# Schematic.net
KiCad netlist of a schematic drawn in EAGLE
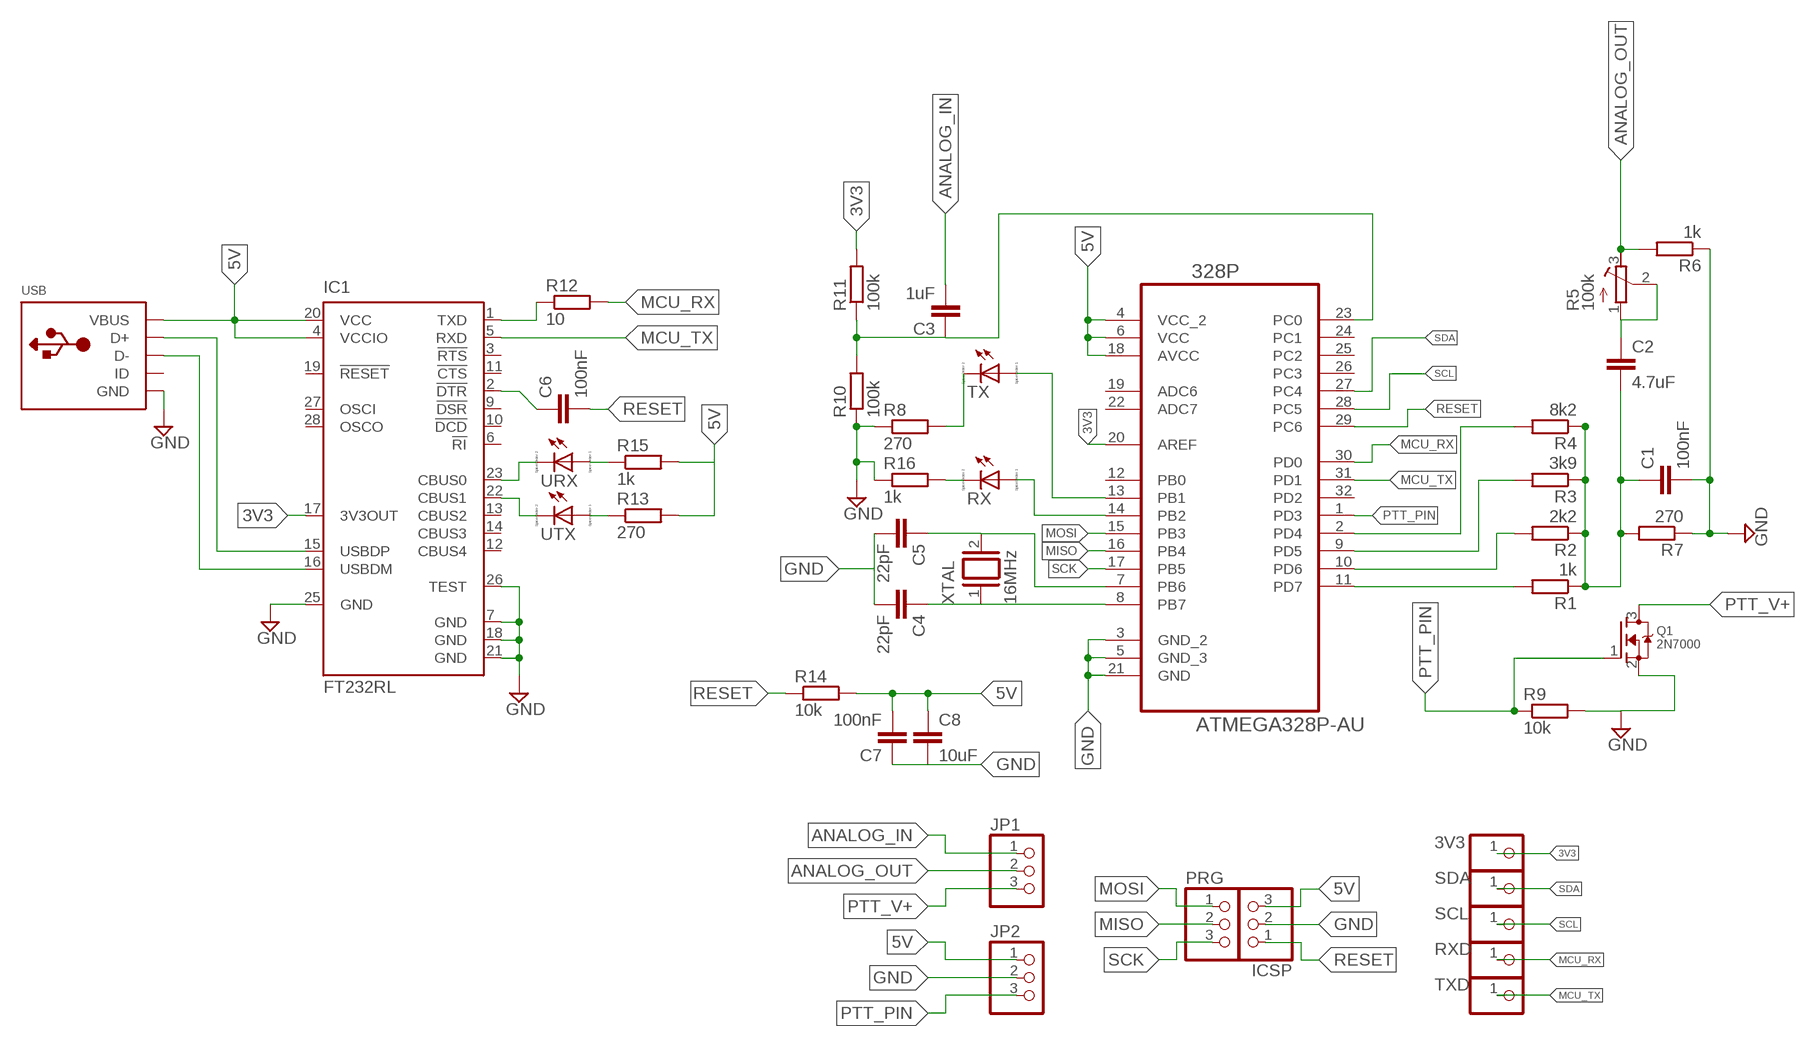
[diagram p0: schematic, sheet 1]

(export (version "E")
  (design (tool "Eeschema 10.0.6"))
  (components
    (comp (ref "3V3")
      (value "PINHD-1X1")
      (footprint "eagle-import:1X01")
      (libsource (lib "eagle-import") (part "PINHD-1X1"))
    )
    (comp (ref "328P")
      (value "ATMEGA328P-AU")
      (footprint "eagle-import:QFP80P900X900X120-32N")
      (libsource (lib "eagle-import") (part "ATMEGA328P-AU"))
    )
    (comp (ref "C1")
      (value "100nF")
      (footprint "eagle-import:C0603")
      (libsource (lib "eagle-import") (part "C-EUC0603"))
    )
    (comp (ref "C2")
      (value "4.7uF")
      (footprint "eagle-import:C0805")
      (libsource (lib "eagle-import") (part "C-EUC0805"))
    )
    (comp (ref "C3")
      (value "1uF")
      (footprint "eagle-import:C0603")
      (libsource (lib "eagle-import") (part "C-EUC0603"))
    )
    (comp (ref "C4")
      (value "22pF")
      (footprint "eagle-import:C0603")
      (libsource (lib "eagle-import") (part "C-EUC0603"))
    )
    (comp (ref "C5")
      (value "22pF")
      (footprint "eagle-import:C0603")
      (libsource (lib "eagle-import") (part "C-EUC0603"))
    )
    (comp (ref "C6")
      (value "100nF")
      (footprint "eagle-import:C0603")
      (libsource (lib "eagle-import") (part "C-EUC0603"))
    )
    (comp (ref "C7")
      (value "100nF")
      (footprint "eagle-import:C0603")
      (libsource (lib "eagle-import") (part "C-EUC0603"))
    )
    (comp (ref "C8")
      (value "10uF")
      (footprint "eagle-import:C0805")
      (libsource (lib "eagle-import") (part "C-EUC0805"))
    )
    (comp (ref "IC1")
      (value "FT232RL")
      (footprint "eagle-import:SSOP28")
      (libsource (lib "eagle-import") (part "FT232RL"))
    )
    (comp (ref "ICSP")
      (value "PINHD-1X3")
      (footprint "eagle-import:1X03")
      (libsource (lib "eagle-import") (part "PINHD-1X3"))
    )
    (comp (ref "JP1")
      (value "PINHD-1X3")
      (footprint "eagle-import:1X03")
      (libsource (lib "eagle-import") (part "PINHD-1X3"))
    )
    (comp (ref "JP2")
      (value "PINHD-1X3")
      (footprint "eagle-import:1X03")
      (libsource (lib "eagle-import") (part "PINHD-1X3"))
    )
    (comp (ref "PRG")
      (value "PINHD-1X3")
      (footprint "eagle-import:1X03")
      (libsource (lib "eagle-import") (part "PINHD-1X3"))
    )
    (comp (ref "Q1")
      (value "2N7000")
      (footprint "eagle-import:SOT23")
      (libsource (lib "eagle-import") (part "MOSFET-NREFLOW"))
    )
    (comp (ref "R1")
      (value "1k")
      (footprint "eagle-import:R0603")
      (libsource (lib "eagle-import") (part "R-EU_R0603"))
    )
    (comp (ref "R2")
      (value "2k2")
      (footprint "eagle-import:R0603")
      (libsource (lib "eagle-import") (part "R-EU_R0603"))
    )
    (comp (ref "R3")
      (value "3k9")
      (footprint "eagle-import:R0603")
      (libsource (lib "eagle-import") (part "R-EU_R0603"))
    )
    (comp (ref "R4")
      (value "8k2")
      (footprint "eagle-import:R0603")
      (libsource (lib "eagle-import") (part "R-EU_R0603"))
    )
    (comp (ref "R5")
      (value "100k")
      (footprint "eagle-import:RTRIM3339P")
      (libsource (lib "eagle-import") (part "R-TRIMM3339P"))
    )
    (comp (ref "R6")
      (value "1k")
      (footprint "eagle-import:R0603")
      (libsource (lib "eagle-import") (part "R-EU_R0603"))
    )
    (comp (ref "R7")
      (value "270")
      (footprint "eagle-import:R0603")
      (libsource (lib "eagle-import") (part "R-EU_R0603"))
    )
    (comp (ref "R8")
      (value "270")
      (footprint "eagle-import:R0603")
      (libsource (lib "eagle-import") (part "R-EU_R0603"))
    )
    (comp (ref "R9")
      (value "10k")
      (footprint "eagle-import:R0603")
      (libsource (lib "eagle-import") (part "R-EU_R0603"))
    )
    (comp (ref "R10")
      (value "100k")
      (footprint "eagle-import:R0603")
      (libsource (lib "eagle-import") (part "R-EU_R0603"))
    )
    (comp (ref "R11")
      (value "100k")
      (footprint "eagle-import:R0603")
      (libsource (lib "eagle-import") (part "R-EU_R0603"))
    )
    (comp (ref "R12")
      (value "10")
      (footprint "eagle-import:R0603")
      (libsource (lib "eagle-import") (part "R-EU_R0603"))
    )
    (comp (ref "R13")
      (value "270")
      (footprint "eagle-import:R0603")
      (libsource (lib "eagle-import") (part "R-EU_R0603"))
    )
    (comp (ref "R14")
      (value "10k")
      (footprint "eagle-import:R0603")
      (libsource (lib "eagle-import") (part "R-EU_R0603"))
    )
    (comp (ref "R15")
      (value "1k")
      (footprint "eagle-import:R0603")
      (libsource (lib "eagle-import") (part "R-EU_R0603"))
    )
    (comp (ref "R16")
      (value "1k")
      (footprint "eagle-import:R0603")
      (libsource (lib "eagle-import") (part "R-EU_R0603"))
    )
    (comp (ref "RX")
      (value "LED_ESML0603")
      (footprint "eagle-import:LED_SML0603")
      (libsource (lib "eagle-import") (part "LED_ESML0603"))
    )
    (comp (ref "RXD")
      (value "PINHD-1X1")
      (footprint "eagle-import:1X01")
      (libsource (lib "eagle-import") (part "PINHD-1X1"))
    )
    (comp (ref "SCL")
      (value "PINHD-1X1")
      (footprint "eagle-import:1X01")
      (libsource (lib "eagle-import") (part "PINHD-1X1"))
    )
    (comp (ref "SDA")
      (value "PINHD-1X1")
      (footprint "eagle-import:1X01")
      (libsource (lib "eagle-import") (part "PINHD-1X1"))
    )
    (comp (ref "TX")
      (value "LED_ESML0603")
      (footprint "eagle-import:LED_SML0603")
      (libsource (lib "eagle-import") (part "LED_ESML0603"))
    )
    (comp (ref "TXD")
      (value "PINHD-1X1")
      (footprint "eagle-import:1X01")
      (libsource (lib "eagle-import") (part "PINHD-1X1"))
    )
    (comp (ref "URX")
      (value "LED_ESML0603")
      (footprint "eagle-import:LED_SML0603")
      (libsource (lib "eagle-import") (part "LED_ESML0603"))
    )
    (comp (ref "USB")
      (value "USBMOLEX")
      (footprint "eagle-import:USB-MINIB-THM-MOLEX")
      (libsource (lib "eagle-import") (part "USBMOLEX"))
    )
    (comp (ref "UTX")
      (value "LED_ESML0603")
      (footprint "eagle-import:LED_SML0603")
      (libsource (lib "eagle-import") (part "LED_ESML0603"))
    )
    (comp (ref "XTAL")
      (value "16MHz")
      (footprint "eagle-import:QS")
      (libsource (lib "eagle-import") (part "XTAL/S"))
    )
  )
  (nets
    (net (code "1") (name "3V3") (class "Default")
      (node (ref "328P") (pin "20") (pinfunction "AREF_20") (pintype "input"))
      (node (ref "3V3") (pin "1") (pinfunction "1_1") (pintype "passive"))
      (node (ref "IC1") (pin "17") (pinfunction "3V3OUT_17") (pintype "output"))
      (node (ref "R11") (pin "2") (pinfunction "2_2") (pintype "passive"))
    )
    (net (code "2") (name "5V") (class "Default")
      (node (ref "328P") (pin "18") (pinfunction "AVCC_18") (pintype "power_in"))
      (node (ref "328P") (pin "4") (pinfunction "VCC_2_4") (pintype "power_in"))
      (node (ref "328P") (pin "6") (pinfunction "VCC_6") (pintype "power_in"))
      (node (ref "C7") (pin "2") (pinfunction "2_2") (pintype "passive"))
      (node (ref "C8") (pin "1") (pinfunction "1_1") (pintype "passive"))
      (node (ref "IC1") (pin "20") (pinfunction "VCC_20") (pintype "power_in"))
      (node (ref "IC1") (pin "4") (pinfunction "VCCIO_4") (pintype "power_in"))
      (node (ref "ICSP") (pin "3") (pinfunction "3_3") (pintype "passive"))
      (node (ref "JP2") (pin "1") (pinfunction "1_1") (pintype "passive"))
      (node (ref "R13") (pin "2") (pinfunction "2_2") (pintype "passive"))
      (node (ref "R14") (pin "2") (pinfunction "2_2") (pintype "passive"))
      (node (ref "R15") (pin "2") (pinfunction "2_2") (pintype "passive"))
      (node (ref "USB") (pin "VBUS") (pinfunction "VBUS_VBUS") (pintype "power_in"))
    )
    (net (code "3") (name "ANALOG_IN") (class "Default")
      (node (ref "C3") (pin "2") (pinfunction "2_2") (pintype "passive"))
      (node (ref "JP1") (pin "1") (pinfunction "1_1") (pintype "passive"))
    )
    (net (code "4") (name "ANALOG_OUT") (class "Default")
      (node (ref "JP1") (pin "2") (pinfunction "2_2") (pintype "passive"))
      (node (ref "R5") (pin "3") (pinfunction "E_3") (pintype "passive"))
      (node (ref "R6") (pin "2") (pinfunction "2_2") (pintype "passive"))
    )
    (net (code "5") (name "GND") (class "Default")
      (node (ref "328P") (pin "21") (pinfunction "GND_21") (pintype "passive"))
      (node (ref "328P") (pin "3") (pinfunction "GND_2_3") (pintype "passive"))
      (node (ref "328P") (pin "5") (pinfunction "GND_3_5") (pintype "passive"))
      (node (ref "C1") (pin "2") (pinfunction "2_2") (pintype "passive"))
      (node (ref "C4") (pin "2") (pinfunction "2_2") (pintype "passive"))
      (node (ref "C5") (pin "2") (pinfunction "2_2") (pintype "passive"))
      (node (ref "C7") (pin "1") (pinfunction "1_1") (pintype "passive"))
      (node (ref "C8") (pin "2") (pinfunction "2_2") (pintype "passive"))
      (node (ref "IC1") (pin "18") (pinfunction "GND_18") (pintype "power_in"))
      (node (ref "IC1") (pin "21") (pinfunction "GND_21") (pintype "power_in"))
      (node (ref "IC1") (pin "25") (pinfunction "GND_25") (pintype "power_in"))
      (node (ref "IC1") (pin "26") (pinfunction "TEST_26") (pintype "input"))
      (node (ref "IC1") (pin "7") (pinfunction "GND_7") (pintype "power_in"))
      (node (ref "ICSP") (pin "2") (pinfunction "2_2") (pintype "passive"))
      (node (ref "JP2") (pin "2") (pinfunction "2_2") (pintype "passive"))
      (node (ref "Q1") (pin "2") (pinfunction "S_2") (pintype "bidirectional"))
      (node (ref "R10") (pin "1") (pinfunction "1_1") (pintype "passive"))
      (node (ref "R16") (pin "1") (pinfunction "1_1") (pintype "passive"))
      (node (ref "R6") (pin "1") (pinfunction "1_1") (pintype "passive"))
      (node (ref "R7") (pin "1") (pinfunction "1_1") (pintype "passive"))
      (node (ref "R8") (pin "1") (pinfunction "1_1") (pintype "passive"))
      (node (ref "R9") (pin "2") (pinfunction "2_2") (pintype "passive"))
      (node (ref "USB") (pin "GND") (pinfunction "GND_GND") (pintype "power_in"))
    )
    (net (code "6") (name "MCU_RX") (class "Default")
      (node (ref "328P") (pin "30") (pinfunction "PD0_30") (pintype "bidirectional"))
      (node (ref "R12") (pin "2") (pinfunction "2_2") (pintype "passive"))
      (node (ref "RXD") (pin "1") (pinfunction "1_1") (pintype "passive"))
    )
    (net (code "7") (name "MCU_TX") (class "Default")
      (node (ref "328P") (pin "31") (pinfunction "PD1_31") (pintype "bidirectional"))
      (node (ref "IC1") (pin "5") (pinfunction "RXD_5") (pintype "input"))
      (node (ref "TXD") (pin "1") (pinfunction "1_1") (pintype "passive"))
    )
    (net (code "8") (name "MISO") (class "Default")
      (node (ref "328P") (pin "16") (pinfunction "PB4_16") (pintype "bidirectional"))
      (node (ref "PRG") (pin "2") (pinfunction "2_2") (pintype "passive"))
    )
    (net (code "9") (name "MOSI") (class "Default")
      (node (ref "328P") (pin "15") (pinfunction "PB3_15") (pintype "bidirectional"))
      (node (ref "PRG") (pin "1") (pinfunction "1_1") (pintype "passive"))
    )
    (net (code "10") (name "Net-(328P-PB1)") (class "Default")
      (node (ref "328P") (pin "13") (pinfunction "PB1_13") (pintype "bidirectional"))
      (node (ref "TX") (pin "A") (pinfunction "A_A") (pintype "passive"))
    )
    (net (code "11") (name "Net-(328P-PB2)") (class "Default")
      (node (ref "328P") (pin "14") (pinfunction "PB2_14") (pintype "bidirectional"))
      (node (ref "RX") (pin "A") (pinfunction "A_A") (pintype "passive"))
    )
    (net (code "12") (name "Net-(328P-PB6)") (class "Default")
      (node (ref "328P") (pin "7") (pinfunction "PB6_7") (pintype "bidirectional"))
      (node (ref "C5") (pin "1") (pinfunction "1_1") (pintype "passive"))
      (node (ref "XTAL") (pin "2") (pinfunction "2_2") (pintype "passive"))
    )
    (net (code "13") (name "Net-(328P-PB7)") (class "Default")
      (node (ref "328P") (pin "8") (pinfunction "PB7_8") (pintype "bidirectional"))
      (node (ref "C4") (pin "1") (pinfunction "1_1") (pintype "passive"))
      (node (ref "XTAL") (pin "1") (pinfunction "1_1") (pintype "passive"))
    )
    (net (code "14") (name "Net-(328P-PC0)") (class "Default")
      (node (ref "328P") (pin "23") (pinfunction "PC0_23") (pintype "bidirectional"))
      (node (ref "C3") (pin "1") (pinfunction "1_1") (pintype "passive"))
      (node (ref "R10") (pin "2") (pinfunction "2_2") (pintype "passive"))
      (node (ref "R11") (pin "1") (pinfunction "1_1") (pintype "passive"))
    )
    (net (code "15") (name "Net-(328P-PD4)") (class "Default")
      (node (ref "328P") (pin "2") (pinfunction "PD4_2") (pintype "bidirectional"))
      (node (ref "R4") (pin "2") (pinfunction "2_2") (pintype "passive"))
    )
    (net (code "16") (name "Net-(328P-PD5)") (class "Default")
      (node (ref "328P") (pin "9") (pinfunction "PD5_9") (pintype "bidirectional"))
      (node (ref "R3") (pin "2") (pinfunction "2_2") (pintype "passive"))
    )
    (net (code "17") (name "Net-(328P-PD6)") (class "Default")
      (node (ref "328P") (pin "10") (pinfunction "PD6_10") (pintype "bidirectional"))
      (node (ref "R2") (pin "2") (pinfunction "2_2") (pintype "passive"))
    )
    (net (code "18") (name "Net-(328P-PD7)") (class "Default")
      (node (ref "328P") (pin "11") (pinfunction "PD7_11") (pintype "bidirectional"))
      (node (ref "R1") (pin "2") (pinfunction "2_2") (pintype "passive"))
    )
    (net (code "19") (name "Net-(C1-Pad1)") (class "Default")
      (node (ref "C1") (pin "1") (pinfunction "1_1") (pintype "passive"))
      (node (ref "C2") (pin "2") (pinfunction "2_2") (pintype "passive"))
      (node (ref "R1") (pin "1") (pinfunction "1_1") (pintype "passive"))
      (node (ref "R2") (pin "1") (pinfunction "1_1") (pintype "passive"))
      (node (ref "R3") (pin "1") (pinfunction "1_1") (pintype "passive"))
      (node (ref "R4") (pin "1") (pinfunction "1_1") (pintype "passive"))
      (node (ref "R7") (pin "2") (pinfunction "2_2") (pintype "passive"))
    )
    (net (code "20") (name "Net-(IC1-CBUS0)") (class "Default")
      (node (ref "IC1") (pin "23") (pinfunction "CBUS0_23") (pintype "bidirectional"))
      (node (ref "URX") (pin "C") (pinfunction "C_C") (pintype "passive"))
    )
    (net (code "21") (name "Net-(IC1-CBUS1)") (class "Default")
      (node (ref "IC1") (pin "22") (pinfunction "CBUS1_22") (pintype "bidirectional"))
      (node (ref "UTX") (pin "C") (pinfunction "C_C") (pintype "passive"))
    )
    (net (code "22") (name "Net-(IC1-TXD)") (class "Default")
      (node (ref "IC1") (pin "1") (pinfunction "TXD_1") (pintype "output"))
      (node (ref "R12") (pin "1") (pinfunction "1_1") (pintype "passive"))
    )
    (net (code "23") (name "Net-(IC1-USBDM)") (class "Default")
      (node (ref "IC1") (pin "16") (pinfunction "USBDM_16") (pintype "bidirectional"))
      (node (ref "USB") (pin "D-") (pinfunction "D-_D-") (pintype "bidirectional"))
    )
    (net (code "24") (name "Net-(IC1-USBDP)") (class "Default")
      (node (ref "IC1") (pin "15") (pinfunction "USBDP_15") (pintype "bidirectional"))
      (node (ref "USB") (pin "D+") (pinfunction "D+_D+") (pintype "bidirectional"))
    )
    (net (code "25") (name "Net-(IC1-~{DTR})") (class "Default")
      (node (ref "C6") (pin "1") (pinfunction "1_1") (pintype "passive"))
      (node (ref "IC1") (pin "2") (pinfunction "~{DTR}_2") (pintype "output"))
    )
    (net (code "26") (name "Net-(R5-A)") (class "Default")
      (node (ref "C2") (pin "1") (pinfunction "1_1") (pintype "passive"))
      (node (ref "R5") (pin "1") (pinfunction "A_1") (pintype "passive"))
      (node (ref "R5") (pin "2") (pinfunction "S_2") (pintype "passive"))
    )
    (net (code "27") (name "Net-(R8-Pad2)") (class "Default")
      (node (ref "R8") (pin "2") (pinfunction "2_2") (pintype "passive"))
      (node (ref "TX") (pin "C") (pinfunction "C_C") (pintype "passive"))
    )
    (net (code "28") (name "Net-(R13-Pad1)") (class "Default")
      (node (ref "R13") (pin "1") (pinfunction "1_1") (pintype "passive"))
      (node (ref "UTX") (pin "A") (pinfunction "A_A") (pintype "passive"))
    )
    (net (code "29") (name "Net-(R15-Pad1)") (class "Default")
      (node (ref "R15") (pin "1") (pinfunction "1_1") (pintype "passive"))
      (node (ref "URX") (pin "A") (pinfunction "A_A") (pintype "passive"))
    )
    (net (code "30") (name "Net-(R16-Pad2)") (class "Default")
      (node (ref "R16") (pin "2") (pinfunction "2_2") (pintype "passive"))
      (node (ref "RX") (pin "C") (pinfunction "C_C") (pintype "passive"))
    )
    (net (code "31") (name "PTT_PIN") (class "Default")
      (node (ref "328P") (pin "1") (pinfunction "PD3_1") (pintype "bidirectional"))
      (node (ref "JP2") (pin "3") (pinfunction "3_3") (pintype "passive"))
      (node (ref "Q1") (pin "1") (pinfunction "G_1") (pintype "bidirectional"))
      (node (ref "R9") (pin "1") (pinfunction "1_1") (pintype "passive"))
    )
    (net (code "32") (name "PTT_V+") (class "Default")
      (node (ref "JP1") (pin "3") (pinfunction "3_3") (pintype "passive"))
      (node (ref "Q1") (pin "3") (pinfunction "D_3") (pintype "bidirectional"))
    )
    (net (code "33") (name "RESET") (class "Default")
      (node (ref "328P") (pin "29") (pinfunction "PC6_29") (pintype "bidirectional"))
      (node (ref "C6") (pin "2") (pinfunction "2_2") (pintype "passive"))
      (node (ref "ICSP") (pin "1") (pinfunction "1_1") (pintype "passive"))
      (node (ref "R14") (pin "1") (pinfunction "1_1") (pintype "passive"))
    )
    (net (code "34") (name "SCK") (class "Default")
      (node (ref "328P") (pin "17") (pinfunction "PB5_17") (pintype "bidirectional"))
      (node (ref "PRG") (pin "3") (pinfunction "3_3") (pintype "passive"))
    )
    (net (code "35") (name "SCL") (class "Default")
      (node (ref "328P") (pin "28") (pinfunction "PC5_28") (pintype "bidirectional"))
      (node (ref "SCL") (pin "1") (pinfunction "1_1") (pintype "passive"))
    )
    (net (code "36") (name "SDA") (class "Default")
      (node (ref "328P") (pin "27") (pinfunction "PC4_27") (pintype "bidirectional"))
      (node (ref "SDA") (pin "1") (pinfunction "1_1") (pintype "passive"))
    )
    (net (code "37") (name "unconnected-(328P-ADC6-Pad19)") (class "Default")
      (node (ref "328P") (pin "19") (pinfunction "ADC6_19") (pintype "input"))
    )
    (net (code "38") (name "unconnected-(328P-ADC7-Pad22)") (class "Default")
      (node (ref "328P") (pin "22") (pinfunction "ADC7_22") (pintype "input"))
    )
    (net (code "39") (name "unconnected-(328P-PB0-Pad12)") (class "Default")
      (node (ref "328P") (pin "12") (pinfunction "PB0_12") (pintype "bidirectional"))
    )
    (net (code "40") (name "unconnected-(328P-PC1-Pad24)") (class "Default")
      (node (ref "328P") (pin "24") (pinfunction "PC1_24") (pintype "bidirectional"))
    )
    (net (code "41") (name "unconnected-(328P-PC2-Pad25)") (class "Default")
      (node (ref "328P") (pin "25") (pinfunction "PC2_25") (pintype "bidirectional"))
    )
    (net (code "42") (name "unconnected-(328P-PC3-Pad26)") (class "Default")
      (node (ref "328P") (pin "26") (pinfunction "PC3_26") (pintype "bidirectional"))
    )
    (net (code "43") (name "unconnected-(328P-PD2-Pad32)") (class "Default")
      (node (ref "328P") (pin "32") (pinfunction "PD2_32") (pintype "bidirectional"))
    )
    (net (code "44") (name "unconnected-(IC1-CBUS2-Pad13)") (class "Default")
      (node (ref "IC1") (pin "13") (pinfunction "CBUS2_13") (pintype "bidirectional"))
    )
    (net (code "45") (name "unconnected-(IC1-CBUS3-Pad14)") (class "Default")
      (node (ref "IC1") (pin "14") (pinfunction "CBUS3_14") (pintype "bidirectional"))
    )
    (net (code "46") (name "unconnected-(IC1-CBUS4-Pad12)") (class "Default")
      (node (ref "IC1") (pin "12") (pinfunction "CBUS4_12") (pintype "bidirectional"))
    )
    (net (code "47") (name "unconnected-(IC1-OSCI-Pad27)") (class "Default")
      (node (ref "IC1") (pin "27") (pinfunction "OSCI_27") (pintype "input"))
    )
    (net (code "48") (name "unconnected-(IC1-OSCO-Pad28)") (class "Default")
      (node (ref "IC1") (pin "28") (pinfunction "OSCO_28") (pintype "output"))
    )
    (net (code "49") (name "unconnected-(IC1-~{CTS}-Pad11)") (class "Default")
      (node (ref "IC1") (pin "11") (pinfunction "~{CTS}_11") (pintype "input"))
    )
    (net (code "50") (name "unconnected-(IC1-~{DCD}-Pad10)") (class "Default")
      (node (ref "IC1") (pin "10") (pinfunction "~{DCD}_10") (pintype "input"))
    )
    (net (code "51") (name "unconnected-(IC1-~{DSR}-Pad9)") (class "Default")
      (node (ref "IC1") (pin "9") (pinfunction "~{DSR}_9") (pintype "input"))
    )
    (net (code "52") (name "unconnected-(IC1-~{RESET}-Pad19)") (class "Default")
      (node (ref "IC1") (pin "19") (pinfunction "~{RESET}_19") (pintype "input"))
    )
    (net (code "53") (name "unconnected-(IC1-~{RI}-Pad6)") (class "Default")
      (node (ref "IC1") (pin "6") (pinfunction "~{RI}_6") (pintype "input"))
    )
    (net (code "54") (name "unconnected-(IC1-~{RTS}-Pad3)") (class "Default")
      (node (ref "IC1") (pin "3") (pinfunction "~{RTS}_3") (pintype "output"))
    )
    (net (code "55") (name "unconnected-(USB-PadID)") (class "Default")
      (node (ref "USB") (pin "ID") (pinfunction "ID_ID") (pintype "bidirectional"))
    )
  )
)
